# MCU.net
KiCad netlist of a schematic drawn in Altium Designer
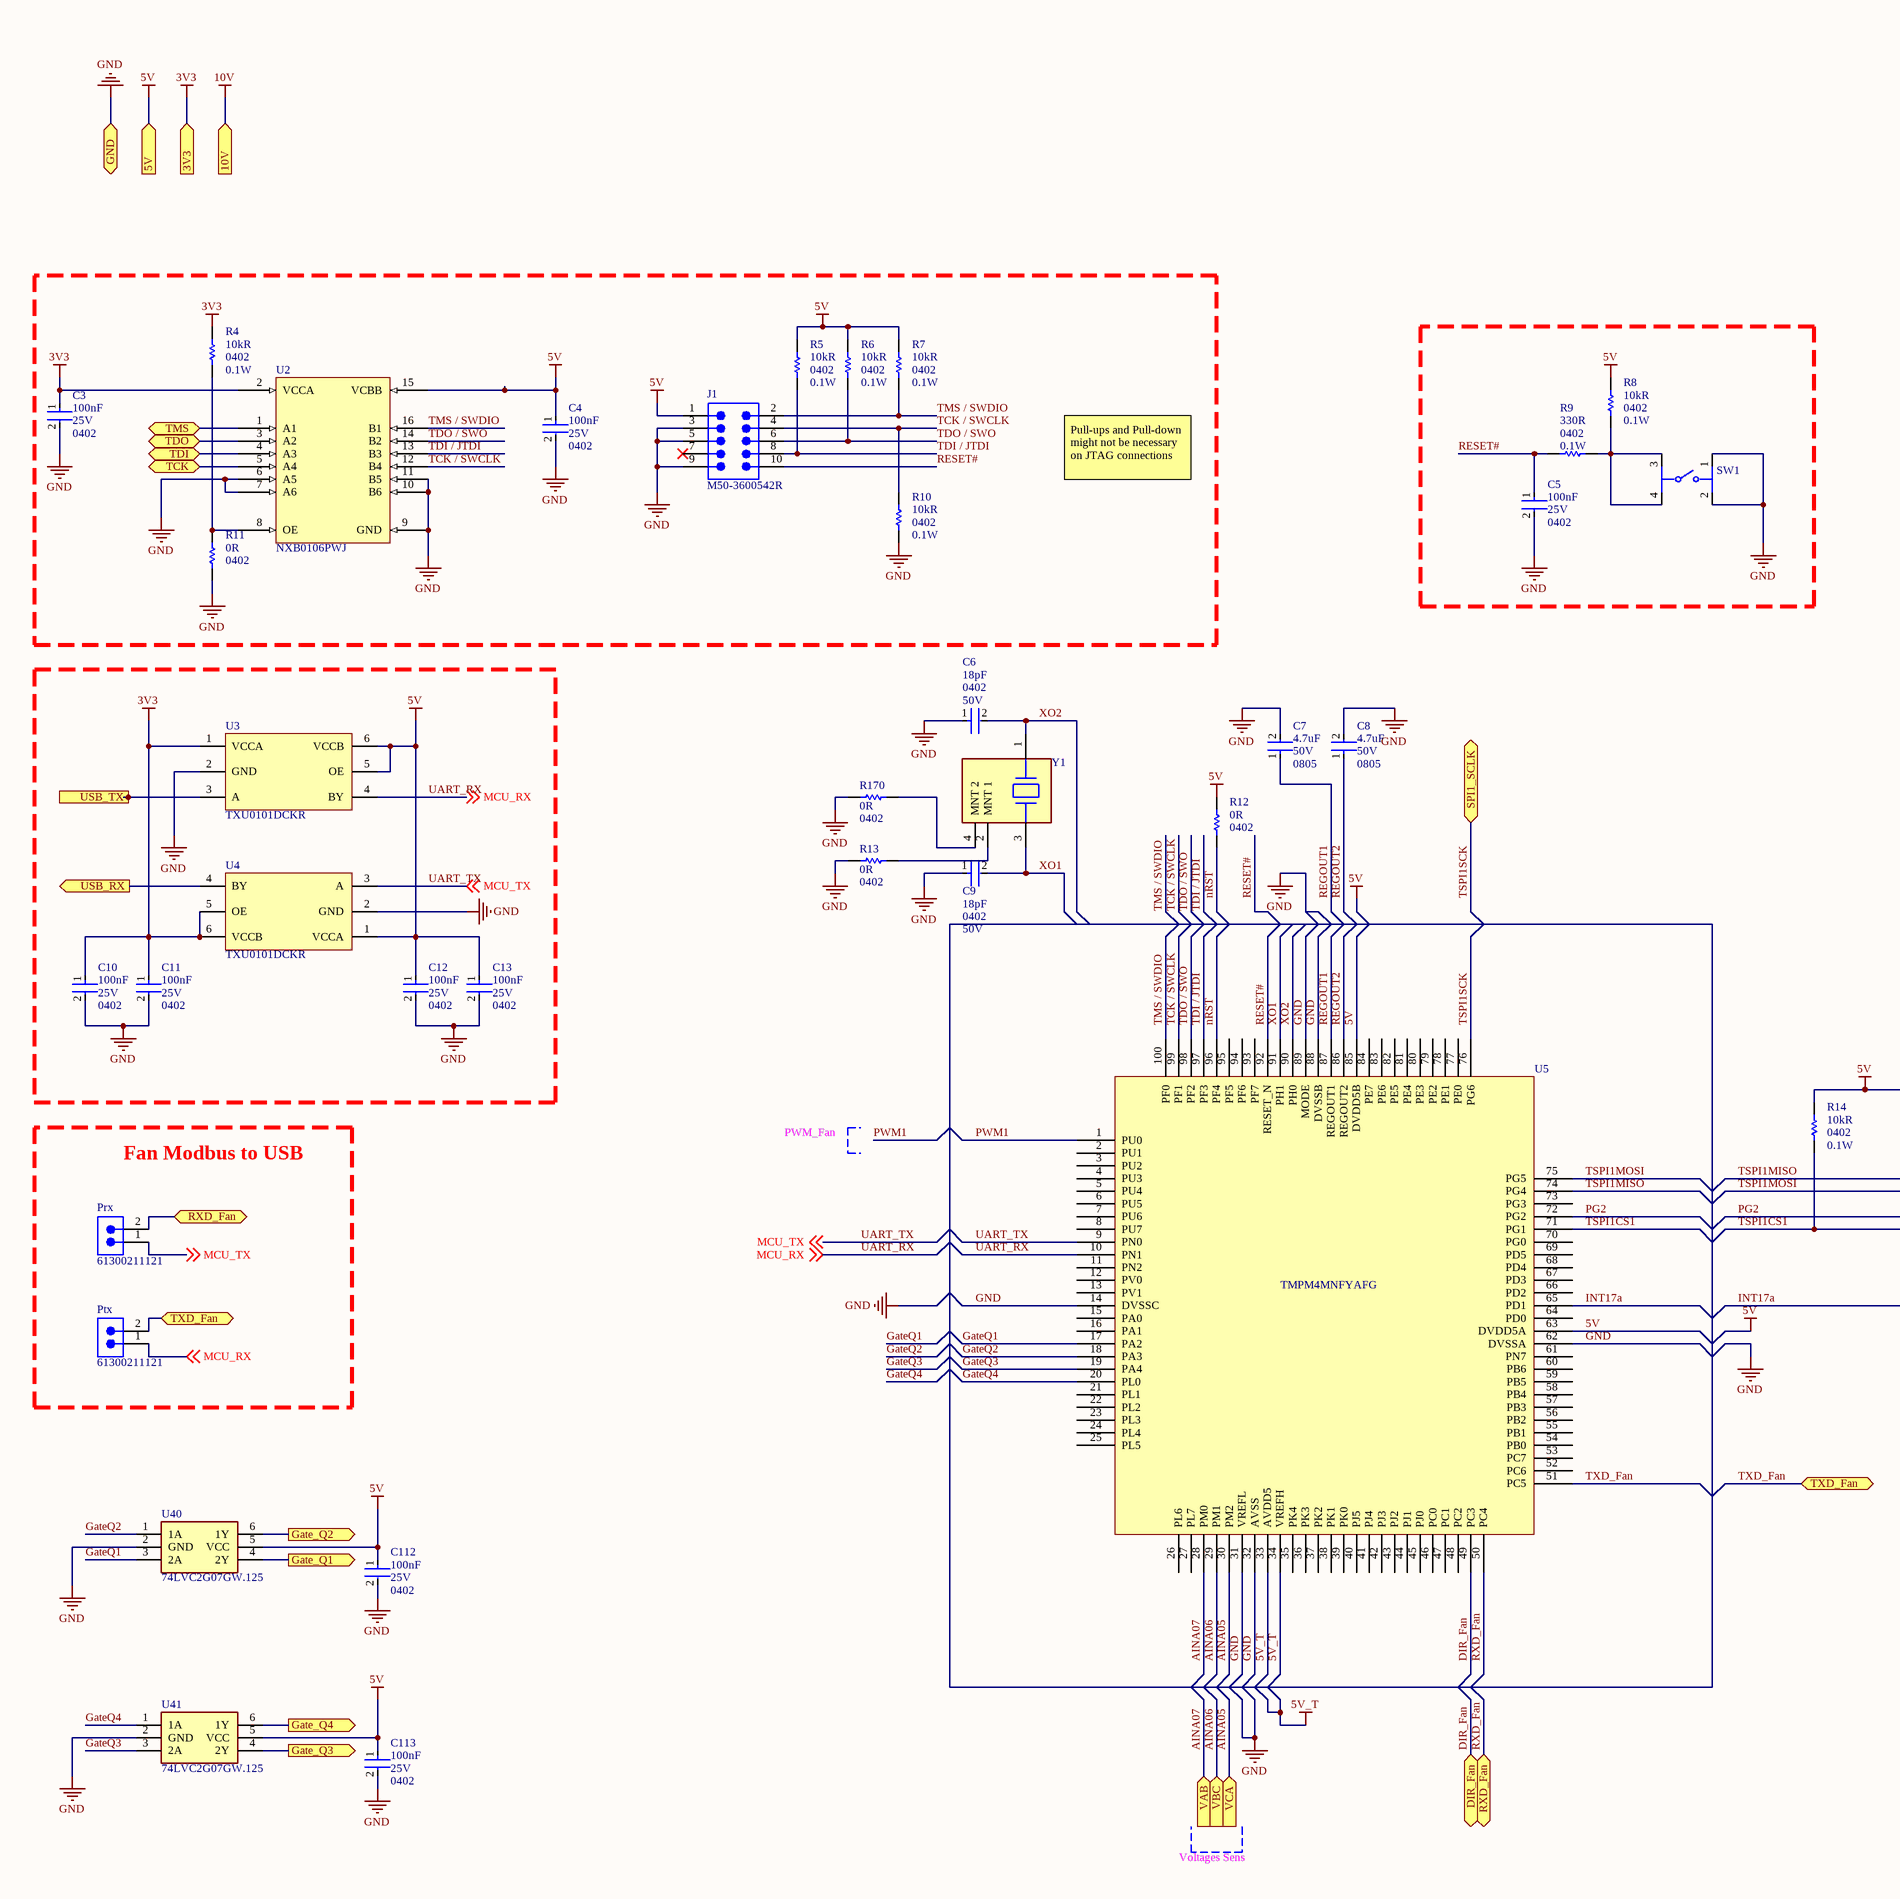
[diagram p0: MCU.SchDoc, left]
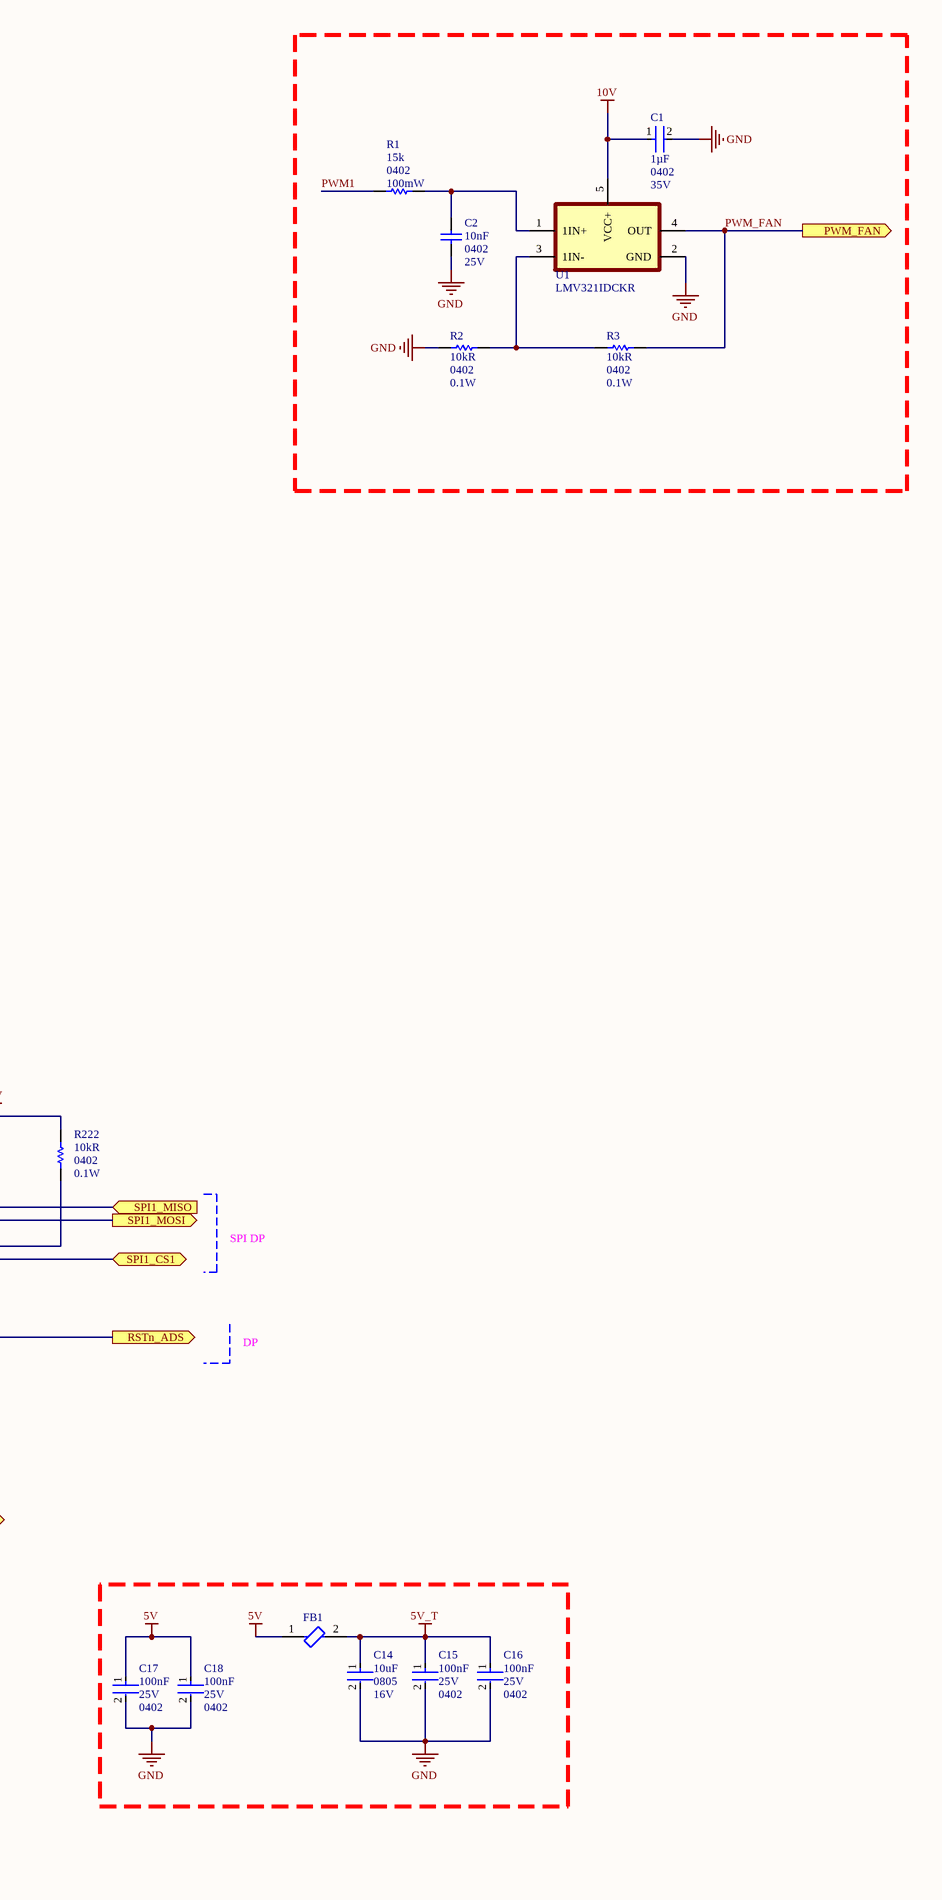
[diagram p1: MCU.SchDoc, right]

(export (version "E")
  (design (tool "Eeschema 10.0.6"))
  (components
    (comp (ref "C1")
      (value "1µF")
      (footprint "FP-C1005-050-0_05-IPC_A")
      (fields
        (field (name "CASE/PACKAGE") "0402")
        (field (name "VOLTAGE RATING") "35V")
        (field (name "Comment") "C1005JB1V105K050BC")
      )
      (libsource (lib "Digital Shovel") (part "b4654b650e69147ec39a6b967a45e02"))
    )
    (comp (ref "C2")
      (value "10nF")
      (footprint "CAPC1005X55X25ML05T10")
      (fields
        (field (name "MANUFACTURER") "Murata")
        (field (name "PACKAGE") "0402")
        (field (name "PARAMETER 1") "25V")
        (field (name "Comment") "GRM155R71E103KA01D")
      )
      (libsource (lib "Digital Shovel") (part "CAP"))
    )
    (comp (ref "C3")
      (value "100nF")
      (footprint "FP-CL830-IPC_A")
      (fields
        (field (name "VOLTAGE RATING") "25V")
        (field (name "CASE/PACKAGE") "0402")
        (field (name "Comment") "CL05B104KA5NNNC")
      )
      (libsource (lib "Digital Shovel") (part "b4654b650e69147ec39a6b967a45e02"))
    )
    (comp (ref "C4")
      (value "100nF")
      (footprint "FP-CL830-IPC_A")
      (fields
        (field (name "VOLTAGE RATING") "25V")
        (field (name "CASE/PACKAGE") "0402")
        (field (name "Comment") "CL05B104KA5NNNC")
      )
      (libsource (lib "Digital Shovel") (part "b4654b650e69147ec39a6b967a45e02"))
    )
    (comp (ref "C5")
      (value "100nF")
      (footprint "FP-CL830-IPC_A")
      (fields
        (field (name "VOLTAGE RATING") "25V")
        (field (name "CASE/PACKAGE") "0402")
        (field (name "Comment") "CL05B104KA5NNNC")
      )
      (libsource (lib "Digital Shovel") (part "b4654b650e69147ec39a6b967a45e02"))
    )
    (comp (ref "C6")
      (value "18pF")
      (footprint "FP-GJM155-0_05-IPC_A")
      (fields
        (field (name "CASE/PACKAGE") "0402")
        (field (name "VOLTAGE RATING") "50V")
        (field (name "Comment") "GJM1555C1H180GB01D")
      )
      (libsource (lib "Digital Shovel") (part "02cd4be3c70576c341d710602a673aa"))
    )
    (comp (ref "C7")
      (value "GRM21BR61H475KE51L")
      (footprint "FP-GRM21B-0_15-IPC_B")
      (description "Chip Multilayer Ceramic Capacitors for General Purpose, 0805, 4.7uF, X5R, 15%, 10%, 50V")
      (fields
        (field (name "CASE/PACKAGE") "0805")
        (field (name "CAPACITANCE") "4.7uF")
        (field (name "VOLTAGE RATING") "50V")
        (field (name "TOLERANCE") "10%")
      )
      (libsource (lib "Altium Content Vault") (part "b4654b650e69147ec39a6b967a45e02"))
    )
    (comp (ref "C8")
      (value "GRM21BR61H475KE51L")
      (footprint "FP-GRM21B-0_15-IPC_B")
      (description "Chip Multilayer Ceramic Capacitors for General Purpose, 0805, 4.7uF, X5R, 15%, 10%, 50V")
      (fields
        (field (name "CASE/PACKAGE") "0805")
        (field (name "CAPACITANCE") "4.7uF")
        (field (name "VOLTAGE RATING") "50V")
        (field (name "TOLERANCE") "10%")
      )
      (libsource (lib "Altium Content Vault") (part "b4654b650e69147ec39a6b967a45e02"))
    )
    (comp (ref "C9")
      (value "18pF")
      (footprint "FP-GJM155-0_05-IPC_A")
      (fields
        (field (name "CASE/PACKAGE") "0402")
        (field (name "VOLTAGE RATING") "50V")
        (field (name "Comment") "GJM1555C1H180GB01D")
      )
      (libsource (lib "Digital Shovel") (part "02cd4be3c70576c341d710602a673aa"))
    )
    (comp (ref "C10")
      (value "100nF")
      (footprint "FP-CL830-IPC_A")
      (fields
        (field (name "VOLTAGE RATING") "25V")
        (field (name "CASE/PACKAGE") "0402")
        (field (name "Comment") "CL05B104KA5NNNC")
      )
      (libsource (lib "Digital Shovel") (part "b4654b650e69147ec39a6b967a45e02"))
    )
    (comp (ref "C11")
      (value "100nF")
      (footprint "FP-CL830-IPC_A")
      (fields
        (field (name "VOLTAGE RATING") "25V")
        (field (name "CASE/PACKAGE") "0402")
        (field (name "Comment") "CL05B104KA5NNNC")
      )
      (libsource (lib "Digital Shovel") (part "b4654b650e69147ec39a6b967a45e02"))
    )
    (comp (ref "C12")
      (value "100nF")
      (footprint "FP-CL830-IPC_A")
      (fields
        (field (name "VOLTAGE RATING") "25V")
        (field (name "CASE/PACKAGE") "0402")
        (field (name "Comment") "CL05B104KA5NNNC")
      )
      (libsource (lib "Digital Shovel") (part "b4654b650e69147ec39a6b967a45e02"))
    )
    (comp (ref "C13")
      (value "100nF")
      (footprint "FP-CL830-IPC_A")
      (fields
        (field (name "VOLTAGE RATING") "25V")
        (field (name "CASE/PACKAGE") "0402")
        (field (name "Comment") "CL05B104KA5NNNC")
      )
      (libsource (lib "Digital Shovel") (part "b4654b650e69147ec39a6b967a45e02"))
    )
    (comp (ref "C14")
      (value "GRM21BR61C106KE15K")
      (footprint "FP-GRM21B-0_1-MFG")
      (description "Chip Multilayer Ceramic Capacitors for General Purpose, 0805, 10uF, X5R, 15%, 10%, 16V")
      (fields
        (field (name "CASE CODE (IMPERIAL)") "0805")
        (field (name "VOLTAGE RATING") "16V")
        (field (name "TOLERANCE") "10%")
        (field (name "VOLTAGE") "16V")
        (field (name "CAPACITANCE") "10uF")
      )
      (libsource (lib "Altium Content Vault") (part "b4654b650e69147ec39a6b967a45e02"))
    )
    (comp (ref "C15")
      (value "100nF")
      (footprint "FP-CL830-IPC_A")
      (fields
        (field (name "VOLTAGE RATING") "25V")
        (field (name "CASE/PACKAGE") "0402")
        (field (name "Comment") "CL05B104KA5NNNC")
      )
      (libsource (lib "Digital Shovel") (part "b4654b650e69147ec39a6b967a45e02"))
    )
    (comp (ref "C16")
      (value "100nF")
      (footprint "FP-CL830-IPC_A")
      (fields
        (field (name "VOLTAGE RATING") "25V")
        (field (name "CASE/PACKAGE") "0402")
        (field (name "Comment") "CL05B104KA5NNNC")
      )
      (libsource (lib "Digital Shovel") (part "b4654b650e69147ec39a6b967a45e02"))
    )
    (comp (ref "C17")
      (value "100nF")
      (footprint "FP-CL830-IPC_A")
      (fields
        (field (name "VOLTAGE RATING") "25V")
        (field (name "CASE/PACKAGE") "0402")
        (field (name "Comment") "CL05B104KA5NNNC")
      )
      (libsource (lib "Digital Shovel") (part "b4654b650e69147ec39a6b967a45e02"))
    )
    (comp (ref "C18")
      (value "100nF")
      (footprint "FP-CL830-IPC_A")
      (fields
        (field (name "VOLTAGE RATING") "25V")
        (field (name "CASE/PACKAGE") "0402")
        (field (name "Comment") "CL05B104KA5NNNC")
      )
      (libsource (lib "Digital Shovel") (part "b4654b650e69147ec39a6b967a45e02"))
    )
    (comp (ref "C112")
      (value "100nF")
      (footprint "FP-CL830-IPC_A")
      (fields
        (field (name "VOLTAGE RATING") "25V")
        (field (name "CASE/PACKAGE") "0402")
        (field (name "Comment") "CL05B104KA5NNNC")
      )
      (libsource (lib "Digital Shovel") (part "b4654b650e69147ec39a6b967a45e02"))
    )
    (comp (ref "C113")
      (value "100nF")
      (footprint "FP-CL830-IPC_A")
      (fields
        (field (name "VOLTAGE RATING") "25V")
        (field (name "CASE/PACKAGE") "0402")
        (field (name "Comment") "CL05B104KA5NNNC")
      )
      (libsource (lib "Digital Shovel") (part "b4654b650e69147ec39a6b967a45e02"))
    )
    (comp (ref "FB1")
      (value "MPZ2012S221AT000")
      (footprint "FP-MPZ2012-MFG")
      (description "FERRITE BEAD 220 OHM 0805 1LN")
      (fields (field (name "TOLERANCE") "25%"))
      (libsource (lib "Altium Content Vault") (part "5f30dd21d616792df468990f7003faa"))
    )
    (comp (ref "J1")
      (value "M50-3600542R")
      (footprint "FP-M50-3600542R-MFG")
      (libsource (lib "Digital Shovel") (part "CMP-00130-1"))
    )
    (comp (ref "Prx")
      (value "61300211121")
      (footprint "61300211121")
      (description "WR-PHD Pin Header, THT, Vertical, pitch 2.54mm, 1 Row, 2P")
      (fields (field (name "MANUFACTURER") "Wurth Elektronik"))
      (libsource (lib "Digital Shovel") (part "62000211121"))
    )
    (comp (ref "Ptx")
      (value "61300211121")
      (footprint "61300211121")
      (description "WR-PHD Pin Header, THT, Vertical, pitch 2.54mm, 1 Row, 2P")
      (fields (field (name "MANUFACTURER") "Wurth Elektronik"))
      (libsource (lib "Digital Shovel") (part "62000211121"))
    )
    (comp (ref "R1")
      (value "15k")
      (footprint "RESC1005X40X25LL10T10")
      (fields
        (field (name "TOLERANCE") "1%")
        (field (name "CASE/PACKAGE") "0402")
        (field (name "POWER") "100mW")
        (field (name "Comment") "RK73H1ETTP1502F")
      )
      (libsource (lib "Digital Shovel") (part "RES"))
    )
    (comp (ref "R2")
      (value "10kR")
      (footprint "RESC1005X40X25LL10T10")
      (fields
        (field (name "PACKAGE") "0402")
        (field (name "POWER") "0.1W")
        (field (name "Comment") "RK73H1ETTP1002F")
      )
      (libsource (lib "Digital Shovel") (part "RES"))
    )
    (comp (ref "R3")
      (value "10kR")
      (footprint "RESC1005X40X25LL10T10")
      (fields
        (field (name "PACKAGE") "0402")
        (field (name "POWER") "0.1W")
        (field (name "Comment") "RK73H1ETTP1002F")
      )
      (libsource (lib "Digital Shovel") (part "RES"))
    )
    (comp (ref "R4")
      (value "10kR")
      (footprint "RESC1005X40X25LL10T10")
      (fields
        (field (name "PACKAGE") "0402")
        (field (name "POWER RATING") "0.1W")
        (field (name "Comment") "RK73H1ETTP1002F")
      )
      (libsource (lib "Digital Shovel") (part "RES"))
    )
    (comp (ref "R5")
      (value "10kR")
      (footprint "RESC1005X40X25LL10T10")
      (fields
        (field (name "PACKAGE") "0402")
        (field (name "POWER RATING") "0.1W")
        (field (name "Comment") "RK73H1ETTP1002F")
      )
      (libsource (lib "Digital Shovel") (part "RES"))
    )
    (comp (ref "R6")
      (value "10kR")
      (footprint "RESC1005X40X25LL10T10")
      (fields
        (field (name "PACKAGE") "0402")
        (field (name "POWER RATING") "0.1W")
        (field (name "Comment") "RK73H1ETTP1002F")
      )
      (libsource (lib "Digital Shovel") (part "RES"))
    )
    (comp (ref "R7")
      (value "10kR")
      (footprint "RESC1005X40X25LL10T10")
      (fields
        (field (name "PACKAGE") "0402")
        (field (name "POWER RATING") "0.1W")
        (field (name "Comment") "RK73H1ETTP1002F")
      )
      (libsource (lib "Digital Shovel") (part "RES"))
    )
    (comp (ref "R8")
      (value "10kR")
      (footprint "RESC1005X40X25LL10T10")
      (fields
        (field (name "PACKAGE") "0402")
        (field (name "POWER RATING") "0.1W")
        (field (name "Comment") "RK73H1ETTP1002F")
      )
      (libsource (lib "Digital Shovel") (part "RES"))
    )
    (comp (ref "R9")
      (value "330R")
      (footprint "RESC1005X40X25LL10T10")
      (fields
        (field (name "PACKAGE") "0402")
        (field (name "POWER RATING") "0.1W")
        (field (name "Comment") "RK73H1ETTP3300F")
      )
      (libsource (lib "Digital Shovel") (part "RES"))
    )
    (comp (ref "R10")
      (value "10kR")
      (footprint "RESC1005X40X25LL10T10")
      (fields
        (field (name "PACKAGE") "0402")
        (field (name "POWER RATING") "0.1W")
        (field (name "Comment") "RK73H1ETTP1002F")
      )
      (libsource (lib "Digital Shovel") (part "RES"))
    )
    (comp (ref "R11")
      (value "0R")
      (footprint "FP-RK73Z1E-IPC_B")
      (description "Metal Glaze/thick Film, 0ohm, Surface Mount, 0402")
      (fields (field (name "PACKAGE") "0402") (field (name "Comment") "RK73Z1ETTP"))
      (libsource (lib "Digital Shovel") (part "1029c3af85768c4190bb7ad29bc67b5"))
    )
    (comp (ref "R12")
      (value "0R")
      (footprint "FP-RK73Z1E-IPC_B")
      (description "Metal Glaze/thick Film, 0ohm, Surface Mount, 0402")
      (fields (field (name "PACKAGE") "0402") (field (name "Comment") "RK73Z1ETTP"))
      (libsource (lib "Digital Shovel") (part "1029c3af85768c4190bb7ad29bc67b5"))
    )
    (comp (ref "R13")
      (value "0R")
      (footprint "FP-RK73Z1E-IPC_B")
      (description "Metal Glaze/thick Film, 0ohm, Surface Mount, 0402")
      (fields (field (name "PACKAGE") "0402") (field (name "Comment") "RK73Z1ETTP"))
      (libsource (lib "Digital Shovel") (part "1029c3af85768c4190bb7ad29bc67b5"))
    )
    (comp (ref "R14")
      (value "10kR")
      (footprint "RESC1005X40X25LL10T10")
      (fields
        (field (name "PACKAGE") "0402")
        (field (name "POWER RATING") "0.1W")
        (field (name "Comment") "RK73H1ETTP1002F")
      )
      (libsource (lib "Digital Shovel") (part "RES"))
    )
    (comp (ref "R170")
      (value "0R")
      (footprint "FP-RK73Z1E-IPC_B")
      (description "Metal Glaze/thick Film, 0ohm, Surface Mount, 0402")
      (fields (field (name "PACKAGE") "0402") (field (name "Comment") "RK73Z1ETTP"))
      (libsource (lib "Digital Shovel") (part "1029c3af85768c4190bb7ad29bc67b5"))
    )
    (comp (ref "R222")
      (value "10kR")
      (footprint "RESC1005X40X25LL10T10")
      (fields
        (field (name "PACKAGE") "0402")
        (field (name "POWER RATING") "0.1W")
        (field (name "Comment") "RK73H1ETTP1002F")
      )
      (libsource (lib "Digital Shovel") (part "RES"))
    )
    (comp (ref "SW1")
      (value "PTS810SJM250SMTRLFS")
      (footprint "FP-PTS810SJM250SMTRLFS-MFG")
      (fields (field (name "MANUFACTURER") "C&K"))
      (libsource (lib "Digital Shovel") (part "1adf0dd01260c80cf25a44bfd6b99ba"))
    )
    (comp (ref "U1")
      (value "LMV321IDCKR")
      (footprint "LMV321IDCKR-Footprint-1")
      (description "Operational Amplifier, 1 Func, 7000uV Offset-Max, BIPolar, PDSO5")
      (libsource (lib "Digital Shovel") (part "TLV9104QPWRQ1"))
    )
    (comp (ref "U2")
      (value "NXB0106PWJ")
      (footprint "TSOP65P640X120-16N")
      (description "NXB0106 - Dual supply translating transceiver; auto direction sensing; 3-state")
      (libsource (lib "Digital Shovel") (part "NXB0106PWJ-Symbol-1"))
    )
    (comp (ref "U3")
      (value "TXU0101DCKR")
      (footprint "FP-DCK0006A-MFG")
      (description "Single channel fixed-direction level shifter 6-SC70 -40 to 125")
      (libsource (lib "Digital Shovel") (part "TXU0101DCKR"))
    )
    (comp (ref "U4")
      (value "TXU0101DCKR")
      (footprint "FP-DCK0006A-MFG")
      (description "Single channel fixed-direction level shifter 6-SC70 -40 to 125")
      (libsource (lib "") (part "TXU0101DCKR_1"))
    )
    (comp (ref "U5")
      (value "TMPM4MNFYAFG")
      (footprint "TSQFP50P1600X1600X145-100N")
      (description "Toshiba Micro")
      (libsource (lib "Digital Shovel") (part "TMPM4MNFYAFG"))
    )
    (comp (ref "U40")
      (value "74LVC2G07GW.125")
      (footprint "74LVC2G07GW.125-Footprint-1")
      (description "Buffer, Non-Inverting 2 Element 1 Bit per Element Open Drain Output 6-TSSOP")
      (libsource (lib "Digital Shovel") (part "74LVC2G07GW.125-Symbol-1"))
    )
    (comp (ref "U41")
      (value "74LVC2G07GW.125")
      (footprint "74LVC2G07GW.125-Footprint-1")
      (description "Buffer, Non-Inverting 2 Element 1 Bit per Element Open Drain Output 6-TSSOP")
      (libsource (lib "Digital Shovel") (part "74LVC2G07GW.125-Symbol-1"))
    )
    (comp (ref "Y1")
      (value "ABM10-166-12.000MHZ-T3")
      (footprint "FP-ABM10-166-167-MFG")
      (description "Crystal 12MHz ±10ppm (Tol) ±10ppm (Stability) 8pF FUND 125Ohm 4-Pin SMD T/R")
      (fields (field (name "MANUFACTURER") "TI"))
      (libsource (lib "Digital Shovel") (part "c1e6c4da84e2560fa339d1e93faccc5"))
    )
  )
  (nets
    (net (code "1") (name "/AINA05") (class "Default")
      (node (ref "U5") (pin "30") (pinfunction "PM2_30") (pintype "passive"))
    )
    (net (code "2") (name "/AINA06") (class "Default")
      (node (ref "U5") (pin "29") (pinfunction "PM1_29") (pintype "passive"))
    )
    (net (code "3") (name "/AINA07") (class "Default")
      (node (ref "U5") (pin "28") (pinfunction "PM0_28") (pintype "passive"))
    )
    (net (code "4") (name "/DIR_Fan") (class "Default")
      (node (ref "U5") (pin "49") (pinfunction "PC3_49") (pintype "passive"))
    )
    (net (code "5") (name "/GateQ1") (class "Default")
      (node (ref "U40") (pin "3") (pinfunction "2A_3") (pintype "passive"))
      (node (ref "U5") (pin "17") (pinfunction "PA2_17") (pintype "passive"))
    )
    (net (code "6") (name "/GateQ2") (class "Default")
      (node (ref "U40") (pin "1") (pinfunction "1A_1") (pintype "passive"))
      (node (ref "U5") (pin "18") (pinfunction "PA3_18") (pintype "passive"))
    )
    (net (code "7") (name "/GateQ3") (class "Default")
      (node (ref "U41") (pin "3") (pinfunction "2A_3") (pintype "passive"))
      (node (ref "U5") (pin "19") (pinfunction "PA4_19") (pintype "passive"))
    )
    (net (code "8") (name "/GateQ4") (class "Default")
      (node (ref "U41") (pin "1") (pinfunction "1A_1") (pintype "passive"))
      (node (ref "U5") (pin "20") (pinfunction "PL0_20") (pintype "passive"))
    )
    (net (code "9") (name "/Gate_Q1") (class "Default")
      (node (ref "U40") (pin "4") (pinfunction "2Y_4") (pintype "passive"))
    )
    (net (code "10") (name "/Gate_Q2") (class "Default")
      (node (ref "U40") (pin "6") (pinfunction "1Y_6") (pintype "passive"))
    )
    (net (code "11") (name "/Gate_Q3") (class "Default")
      (node (ref "U41") (pin "4") (pinfunction "2Y_4") (pintype "passive"))
    )
    (net (code "12") (name "/Gate_Q4") (class "Default")
      (node (ref "U41") (pin "6") (pinfunction "1Y_6") (pintype "passive"))
    )
    (net (code "13") (name "/INT17a") (class "Default")
      (node (ref "U5") (pin "65") (pinfunction "PD1_65") (pintype "passive"))
    )
    (net (code "14") (name "/PG2") (class "Default")
      (node (ref "R222") (pin "1") (pinfunction "1_1") (pintype "passive"))
      (node (ref "U5") (pin "72") (pinfunction "PG2_72") (pintype "passive"))
    )
    (net (code "15") (name "/PWM1") (class "Default")
      (node (ref "R1") (pin "1") (pinfunction "1_1") (pintype "passive"))
      (node (ref "U5") (pin "1") (pinfunction "PU0_1") (pintype "passive"))
    )
    (net (code "16") (name "/PWM_FAN") (class "Default")
      (node (ref "R3") (pin "2") (pinfunction "2_2") (pintype "passive"))
      (node (ref "U1") (pin "4") (pinfunction "OUT_4") (pintype "passive"))
    )
    (net (code "17") (name "/REGOUT1") (class "Default")
      (node (ref "C7") (pin "1") (pinfunction "1_1") (pintype "passive"))
      (node (ref "U5") (pin "87") (pinfunction "REGOUT1_87") (pintype "passive"))
    )
    (net (code "18") (name "/REGOUT2") (class "Default")
      (node (ref "C8") (pin "1") (pinfunction "1_1") (pintype "passive"))
      (node (ref "U5") (pin "86") (pinfunction "REGOUT2_86") (pintype "passive"))
    )
    (net (code "19") (name "/RESET#") (class "Default")
      (node (ref "C5") (pin "1") (pinfunction "1_1") (pintype "passive"))
      (node (ref "J1") (pin "10") (pinfunction "10_10") (pintype "passive"))
      (node (ref "R9") (pin "1") (pinfunction "1_1") (pintype "passive"))
      (node (ref "U5") (pin "92") (pinfunction "RESET_N_92") (pintype "passive"))
    )
    (net (code "20") (name "/RXD_Fan") (class "Default")
      (node (ref "Prx") (pin "2") (pinfunction "2_2") (pintype "passive"))
      (node (ref "U5") (pin "50") (pinfunction "PC4_50") (pintype "passive"))
    )
    (net (code "21") (name "/TCK") (class "Default")
      (node (ref "U2") (pin "5") (pinfunction "A4_5") (pintype "input"))
    )
    (net (code "22") (name "/TCK {slash} SWCLK") (class "Default")
      (node (ref "J1") (pin "4") (pinfunction "4_4") (pintype "passive"))
      (node (ref "R10") (pin "2") (pinfunction "2_2") (pintype "passive"))
      (node (ref "U2") (pin "12") (pinfunction "B4_12") (pintype "input"))
      (node (ref "U5") (pin "99") (pinfunction "PF1_99") (pintype "passive"))
    )
    (net (code "23") (name "/TDI") (class "Default")
      (node (ref "U2") (pin "4") (pinfunction "A3_4") (pintype "input"))
    )
    (net (code "24") (name "/TDI {slash} JTDI") (class "Default")
      (node (ref "J1") (pin "8") (pinfunction "8_8") (pintype "passive"))
      (node (ref "R5") (pin "1") (pinfunction "1_1") (pintype "passive"))
      (node (ref "U2") (pin "13") (pinfunction "B3_13") (pintype "input"))
      (node (ref "U5") (pin "97") (pinfunction "PF3_97") (pintype "passive"))
    )
    (net (code "25") (name "/TDO") (class "Default")
      (node (ref "U2") (pin "3") (pinfunction "A2_3") (pintype "input"))
    )
    (net (code "26") (name "/TDO {slash} SWO") (class "Default")
      (node (ref "J1") (pin "6") (pinfunction "6_6") (pintype "passive"))
      (node (ref "R6") (pin "1") (pinfunction "1_1") (pintype "passive"))
      (node (ref "U2") (pin "14") (pinfunction "B2_14") (pintype "input"))
      (node (ref "U5") (pin "98") (pinfunction "PF2_98") (pintype "passive"))
    )
    (net (code "27") (name "/TMS") (class "Default")
      (node (ref "U2") (pin "1") (pinfunction "A1_1") (pintype "input"))
    )
    (net (code "28") (name "/TMS {slash} SWDIO") (class "Default")
      (node (ref "J1") (pin "2") (pinfunction "2_2") (pintype "passive"))
      (node (ref "R7") (pin "1") (pinfunction "1_1") (pintype "passive"))
      (node (ref "U2") (pin "16") (pinfunction "B1_16") (pintype "input"))
      (node (ref "U5") (pin "100") (pinfunction "PF0_100") (pintype "passive"))
    )
    (net (code "29") (name "/TSPI1CS1") (class "Default")
      (node (ref "R14") (pin "1") (pinfunction "1_1") (pintype "passive"))
      (node (ref "U5") (pin "71") (pinfunction "PG1_71") (pintype "passive"))
    )
    (net (code "30") (name "/TSPI1MISO") (class "Default")
      (node (ref "U5") (pin "74") (pinfunction "PG4_74") (pintype "passive"))
    )
    (net (code "31") (name "/TSPI1MOSI") (class "Default")
      (node (ref "U5") (pin "75") (pinfunction "PG5_75") (pintype "passive"))
    )
    (net (code "32") (name "/TSPI1SCK") (class "Default")
      (node (ref "U5") (pin "76") (pinfunction "PG6_76") (pintype "passive"))
    )
    (net (code "33") (name "/TXD_Fan") (class "Default")
      (node (ref "Ptx") (pin "2") (pinfunction "2_2") (pintype "passive"))
      (node (ref "U5") (pin "51") (pinfunction "PC5_51") (pintype "passive"))
    )
    (net (code "34") (name "/USB_RX") (class "Default")
      (node (ref "U4") (pin "4") (pinfunction "BY_4") (pintype "passive"))
    )
    (net (code "35") (name "/USB_TX") (class "Default")
      (node (ref "U3") (pin "3") (pinfunction "A_3") (pintype "passive"))
    )
    (net (code "36") (name "/XO1") (class "Default")
      (node (ref "C9") (pin "2") (pinfunction "2_2") (pintype "passive"))
      (node (ref "U5") (pin "91") (pinfunction "PH1_91") (pintype "passive"))
      (node (ref "Y1") (pin "3") (pinfunction "3_3") (pintype "passive"))
    )
    (net (code "37") (name "/XO2") (class "Default")
      (node (ref "C6") (pin "2") (pinfunction "2_2") (pintype "passive"))
      (node (ref "U5") (pin "90") (pinfunction "PH0_90") (pintype "passive"))
      (node (ref "Y1") (pin "1") (pinfunction "1_1") (pintype "passive"))
    )
    (net (code "38") (name "/nRST") (class "Default")
      (node (ref "R12") (pin "1") (pinfunction "1_1") (pintype "passive"))
      (node (ref "U5") (pin "96") (pinfunction "PF4_96") (pintype "passive"))
    )
    (net (code "39") (name "3V3") (class "Default")
      (node (ref "C10") (pin "1") (pinfunction "1_1") (pintype "passive"))
      (node (ref "C11") (pin "1") (pinfunction "1_1") (pintype "passive"))
      (node (ref "C3") (pin "1") (pinfunction "1_1") (pintype "passive"))
      (node (ref "R4") (pin "2") (pinfunction "2_2") (pintype "passive"))
      (node (ref "U2") (pin "2") (pinfunction "VCCA_2") (pintype "input"))
      (node (ref "U3") (pin "1") (pinfunction "VCCA_1") (pintype "passive"))
      (node (ref "U4") (pin "5") (pinfunction "OE_5") (pintype "passive"))
      (node (ref "U4") (pin "6") (pinfunction "VCCB_6") (pintype "passive"))
    )
    (net (code "40") (name "5V") (class "Default")
      (node (ref "C112") (pin "1") (pinfunction "1_1") (pintype "passive"))
      (node (ref "C113") (pin "1") (pinfunction "1_1") (pintype "passive"))
      (node (ref "C12") (pin "1") (pinfunction "1_1") (pintype "passive"))
      (node (ref "C13") (pin "1") (pinfunction "1_1") (pintype "passive"))
      (node (ref "C17") (pin "1") (pinfunction "1_1") (pintype "passive"))
      (node (ref "C18") (pin "1") (pinfunction "1_1") (pintype "passive"))
      (node (ref "C4") (pin "1") (pinfunction "1_1") (pintype "passive"))
      (node (ref "FB1") (pin "1") (pinfunction "1_1") (pintype "passive"))
      (node (ref "J1") (pin "1") (pinfunction "1_1") (pintype "passive"))
      (node (ref "R12") (pin "2") (pinfunction "2_2") (pintype "passive"))
      (node (ref "R14") (pin "2") (pinfunction "2_2") (pintype "passive"))
      (node (ref "R222") (pin "2") (pinfunction "2_2") (pintype "passive"))
      (node (ref "R5") (pin "2") (pinfunction "2_2") (pintype "passive"))
      (node (ref "R6") (pin "2") (pinfunction "2_2") (pintype "passive"))
      (node (ref "R7") (pin "2") (pinfunction "2_2") (pintype "passive"))
      (node (ref "R8") (pin "2") (pinfunction "2_2") (pintype "passive"))
      (node (ref "U2") (pin "15") (pinfunction "VCBB_15") (pintype "input"))
      (node (ref "U3") (pin "5") (pinfunction "OE_5") (pintype "passive"))
      (node (ref "U3") (pin "6") (pinfunction "VCCB_6") (pintype "passive"))
      (node (ref "U4") (pin "1") (pinfunction "VCCA_1") (pintype "passive"))
      (node (ref "U40") (pin "5") (pinfunction "VCC_5") (pintype "passive"))
      (node (ref "U41") (pin "5") (pinfunction "VCC_5") (pintype "passive"))
      (node (ref "U5") (pin "63") (pinfunction "DVDD5A_63") (pintype "passive"))
      (node (ref "U5") (pin "85") (pinfunction "DVDD5B_85") (pintype "passive"))
    )
    (net (code "41") (name "5V_T") (class "Default")
      (node (ref "C14") (pin "1") (pinfunction "1_1") (pintype "passive"))
      (node (ref "C15") (pin "1") (pinfunction "1_1") (pintype "passive"))
      (node (ref "C16") (pin "1") (pinfunction "1_1") (pintype "passive"))
      (node (ref "FB1") (pin "2") (pinfunction "2_2") (pintype "passive"))
      (node (ref "U5") (pin "33") (pinfunction "AVDD5_33") (pintype "passive"))
      (node (ref "U5") (pin "34") (pinfunction "VREFH_34") (pintype "passive"))
    )
    (net (code "42") (name "10V") (class "Default")
      (node (ref "C1") (pin "1") (pinfunction "1_1") (pintype "passive"))
      (node (ref "U1") (pin "5") (pinfunction "VCC+_5") (pintype "passive"))
    )
    (net (code "43") (name "GND") (class "Default")
      (node (ref "C1") (pin "2") (pinfunction "2_2") (pintype "passive"))
      (node (ref "C10") (pin "2") (pinfunction "2_2") (pintype "passive"))
      (node (ref "C11") (pin "2") (pinfunction "2_2") (pintype "passive"))
      (node (ref "C112") (pin "2") (pinfunction "2_2") (pintype "passive"))
      (node (ref "C113") (pin "2") (pinfunction "2_2") (pintype "passive"))
      (node (ref "C12") (pin "2") (pinfunction "2_2") (pintype "passive"))
      (node (ref "C13") (pin "2") (pinfunction "2_2") (pintype "passive"))
      (node (ref "C14") (pin "2") (pinfunction "2_2") (pintype "passive"))
      (node (ref "C15") (pin "2") (pinfunction "2_2") (pintype "passive"))
      (node (ref "C16") (pin "2") (pinfunction "2_2") (pintype "passive"))
      (node (ref "C17") (pin "2") (pinfunction "2_2") (pintype "passive"))
      (node (ref "C18") (pin "2") (pinfunction "2_2") (pintype "passive"))
      (node (ref "C2") (pin "1") (pinfunction "1_1") (pintype "passive"))
      (node (ref "C3") (pin "2") (pinfunction "2_2") (pintype "passive"))
      (node (ref "C4") (pin "2") (pinfunction "2_2") (pintype "passive"))
      (node (ref "C5") (pin "2") (pinfunction "2_2") (pintype "passive"))
      (node (ref "C6") (pin "1") (pinfunction "1_1") (pintype "passive"))
      (node (ref "C7") (pin "2") (pinfunction "2_2") (pintype "passive"))
      (node (ref "C8") (pin "2") (pinfunction "2_2") (pintype "passive"))
      (node (ref "C9") (pin "1") (pinfunction "1_1") (pintype "passive"))
      (node (ref "J1") (pin "3") (pinfunction "3_3") (pintype "passive"))
      (node (ref "J1") (pin "5") (pinfunction "5_5") (pintype "passive"))
      (node (ref "J1") (pin "9") (pinfunction "9_9") (pintype "passive"))
      (node (ref "R10") (pin "1") (pinfunction "1_1") (pintype "passive"))
      (node (ref "R11") (pin "1") (pinfunction "1_1") (pintype "passive"))
      (node (ref "R13") (pin "2") (pinfunction "2_2") (pintype "passive"))
      (node (ref "R170") (pin "2") (pinfunction "2_2") (pintype "passive"))
      (node (ref "R2") (pin "1") (pinfunction "1_1") (pintype "passive"))
      (node (ref "SW1") (pin "1") (pinfunction "1_1") (pintype "passive"))
      (node (ref "SW1") (pin "2") (pinfunction "2_2") (pintype "passive"))
      (node (ref "U1") (pin "2") (pinfunction "GND_2") (pintype "passive"))
      (node (ref "U2") (pin "10") (pinfunction "B6_10") (pintype "input"))
      (node (ref "U2") (pin "11") (pinfunction "B5_11") (pintype "input"))
      (node (ref "U2") (pin "6") (pinfunction "A5_6") (pintype "input"))
      (node (ref "U2") (pin "7") (pinfunction "A6_7") (pintype "input"))
      (node (ref "U2") (pin "9") (pinfunction "GND_9") (pintype "input"))
      (node (ref "U3") (pin "2") (pinfunction "GND_2") (pintype "passive"))
      (node (ref "U4") (pin "2") (pinfunction "GND_2") (pintype "passive"))
      (node (ref "U40") (pin "2") (pinfunction "GND_2") (pintype "passive"))
      (node (ref "U41") (pin "2") (pinfunction "GND_2") (pintype "passive"))
      (node (ref "U5") (pin "14") (pinfunction "DVSSC_14") (pintype "passive"))
      (node (ref "U5") (pin "31") (pinfunction "VREFL_31") (pintype "passive"))
      (node (ref "U5") (pin "32") (pinfunction "AVSS_32") (pintype "passive"))
      (node (ref "U5") (pin "62") (pinfunction "DVSSA_62") (pintype "passive"))
      (node (ref "U5") (pin "88") (pinfunction "DVSSB_88") (pintype "passive"))
      (node (ref "U5") (pin "89") (pinfunction "MODE_89") (pintype "passive"))
    )
    (net (code "44") (name "MCU_RX") (class "Default")
      (node (ref "Ptx") (pin "1") (pinfunction "1_1") (pintype "passive"))
      (node (ref "U3") (pin "4") (pinfunction "BY_4") (pintype "passive"))
      (node (ref "U5") (pin "10") (pinfunction "PN1_10") (pintype "passive"))
    )
    (net (code "45") (name "MCU_TX") (class "Default")
      (node (ref "Prx") (pin "1") (pinfunction "1_1") (pintype "passive"))
      (node (ref "U4") (pin "3") (pinfunction "A_3") (pintype "passive"))
      (node (ref "U5") (pin "9") (pinfunction "PN0_9") (pintype "passive"))
    )
    (net (code "46") (name "Net-(R8-Pad1)") (class "Default")
      (node (ref "R8") (pin "1") (pinfunction "1_1") (pintype "passive"))
      (node (ref "R9") (pin "2") (pinfunction "2_2") (pintype "passive"))
      (node (ref "SW1") (pin "3") (pinfunction "3_3") (pintype "passive"))
      (node (ref "SW1") (pin "4") (pinfunction "4_4") (pintype "passive"))
    )
    (net (code "47") (name "Net-(U1-1IN+)") (class "Default")
      (node (ref "C2") (pin "2") (pinfunction "2_2") (pintype "passive"))
      (node (ref "R1") (pin "2") (pinfunction "2_2") (pintype "passive"))
      (node (ref "U1") (pin "1") (pinfunction "1IN+_1") (pintype "passive"))
    )
    (net (code "48") (name "Net-(U1-1IN-)") (class "Default")
      (node (ref "R2") (pin "2") (pinfunction "2_2") (pintype "passive"))
      (node (ref "R3") (pin "1") (pinfunction "1_1") (pintype "passive"))
      (node (ref "U1") (pin "3") (pinfunction "1IN-_3") (pintype "passive"))
    )
    (net (code "49") (name "Net-(U2-OE)") (class "Default")
      (node (ref "R11") (pin "2") (pinfunction "2_2") (pintype "passive"))
      (node (ref "R4") (pin "1") (pinfunction "1_1") (pintype "passive"))
      (node (ref "U2") (pin "8") (pinfunction "OE_8") (pintype "input"))
    )
    (net (code "50") (name "Net-(Y1-MNT_1)") (class "Default")
      (node (ref "R13") (pin "1") (pinfunction "1_1") (pintype "passive"))
      (node (ref "Y1") (pin "2") (pinfunction "MNT_1_2") (pintype "passive"))
    )
    (net (code "51") (name "Net-(Y1-MNT_2)") (class "Default")
      (node (ref "R170") (pin "1") (pinfunction "1_1") (pintype "passive"))
      (node (ref "Y1") (pin "4") (pinfunction "MNT_2_4") (pintype "passive"))
    )
    (net (code "52") (name "unconnected-(J1-Pad7)") (class "Default")
      (node (ref "J1") (pin "7") (pinfunction "7_7") (pintype "passive+no_connect"))
    )
    (net (code "53") (name "unconnected-(U5-PA0-Pad15)") (class "Default")
      (node (ref "U5") (pin "15") (pinfunction "PA0_15") (pintype "passive"))
    )
    (net (code "54") (name "unconnected-(U5-PA1-Pad16)") (class "Default")
      (node (ref "U5") (pin "16") (pinfunction "PA1_16") (pintype "passive"))
    )
    (net (code "55") (name "unconnected-(U5-PB0-Pad54)") (class "Default")
      (node (ref "U5") (pin "54") (pinfunction "PB0_54") (pintype "passive"))
    )
    (net (code "56") (name "unconnected-(U5-PB1-Pad55)") (class "Default")
      (node (ref "U5") (pin "55") (pinfunction "PB1_55") (pintype "passive"))
    )
    (net (code "57") (name "unconnected-(U5-PB2-Pad56)") (class "Default")
      (node (ref "U5") (pin "56") (pinfunction "PB2_56") (pintype "passive"))
    )
    (net (code "58") (name "unconnected-(U5-PB3-Pad57)") (class "Default")
      (node (ref "U5") (pin "57") (pinfunction "PB3_57") (pintype "passive"))
    )
    (net (code "59") (name "unconnected-(U5-PB4-Pad58)") (class "Default")
      (node (ref "U5") (pin "58") (pinfunction "PB4_58") (pintype "passive"))
    )
    (net (code "60") (name "unconnected-(U5-PB5-Pad59)") (class "Default")
      (node (ref "U5") (pin "59") (pinfunction "PB5_59") (pintype "passive"))
    )
    (net (code "61") (name "unconnected-(U5-PB6-Pad60)") (class "Default")
      (node (ref "U5") (pin "60") (pinfunction "PB6_60") (pintype "passive"))
    )
    (net (code "62") (name "unconnected-(U5-PC0-Pad46)") (class "Default")
      (node (ref "U5") (pin "46") (pinfunction "PC0_46") (pintype "passive"))
    )
    (net (code "63") (name "unconnected-(U5-PC1-Pad47)") (class "Default")
      (node (ref "U5") (pin "47") (pinfunction "PC1_47") (pintype "passive"))
    )
    (net (code "64") (name "unconnected-(U5-PC2-Pad48)") (class "Default")
      (node (ref "U5") (pin "48") (pinfunction "PC2_48") (pintype "passive"))
    )
    (net (code "65") (name "unconnected-(U5-PC6-Pad52)") (class "Default")
      (node (ref "U5") (pin "52") (pinfunction "PC6_52") (pintype "passive"))
    )
    (net (code "66") (name "unconnected-(U5-PC7-Pad53)") (class "Default")
      (node (ref "U5") (pin "53") (pinfunction "PC7_53") (pintype "passive"))
    )
    (net (code "67") (name "unconnected-(U5-PD0-Pad64)") (class "Default")
      (node (ref "U5") (pin "64") (pinfunction "PD0_64") (pintype "passive"))
    )
    (net (code "68") (name "unconnected-(U5-PD2-Pad66)") (class "Default")
      (node (ref "U5") (pin "66") (pinfunction "PD2_66") (pintype "passive"))
    )
    (net (code "69") (name "unconnected-(U5-PD3-Pad67)") (class "Default")
      (node (ref "U5") (pin "67") (pinfunction "PD3_67") (pintype "passive"))
    )
    (net (code "70") (name "unconnected-(U5-PD4-Pad68)") (class "Default")
      (node (ref "U5") (pin "68") (pinfunction "PD4_68") (pintype "passive"))
    )
    (net (code "71") (name "unconnected-(U5-PD5-Pad69)") (class "Default")
      (node (ref "U5") (pin "69") (pinfunction "PD5_69") (pintype "passive"))
    )
    (net (code "72") (name "unconnected-(U5-PE0-Pad77)") (class "Default")
      (node (ref "U5") (pin "77") (pinfunction "PE0_77") (pintype "passive"))
    )
    (net (code "73") (name "unconnected-(U5-PE1-Pad78)") (class "Default")
      (node (ref "U5") (pin "78") (pinfunction "PE1_78") (pintype "passive"))
    )
    (net (code "74") (name "unconnected-(U5-PE2-Pad79)") (class "Default")
      (node (ref "U5") (pin "79") (pinfunction "PE2_79") (pintype "passive"))
    )
    (net (code "75") (name "unconnected-(U5-PE3-Pad80)") (class "Default")
      (node (ref "U5") (pin "80") (pinfunction "PE3_80") (pintype "passive"))
    )
    (net (code "76") (name "unconnected-(U5-PE4-Pad81)") (class "Default")
      (node (ref "U5") (pin "81") (pinfunction "PE4_81") (pintype "passive"))
    )
    (net (code "77") (name "unconnected-(U5-PE5-Pad82)") (class "Default")
      (node (ref "U5") (pin "82") (pinfunction "PE5_82") (pintype "passive"))
    )
    (net (code "78") (name "unconnected-(U5-PE6-Pad83)") (class "Default")
      (node (ref "U5") (pin "83") (pinfunction "PE6_83") (pintype "passive"))
    )
    (net (code "79") (name "unconnected-(U5-PE7-Pad84)") (class "Default")
      (node (ref "U5") (pin "84") (pinfunction "PE7_84") (pintype "passive"))
    )
    (net (code "80") (name "unconnected-(U5-PF5-Pad95)") (class "Default")
      (node (ref "U5") (pin "95") (pinfunction "PF5_95") (pintype "passive"))
    )
    (net (code "81") (name "unconnected-(U5-PF6-Pad94)") (class "Default")
      (node (ref "U5") (pin "94") (pinfunction "PF6_94") (pintype "passive"))
    )
    (net (code "82") (name "unconnected-(U5-PF7-Pad93)") (class "Default")
      (node (ref "U5") (pin "93") (pinfunction "PF7_93") (pintype "passive"))
    )
    (net (code "83") (name "unconnected-(U5-PG0-Pad70)") (class "Default")
      (node (ref "U5") (pin "70") (pinfunction "PG0_70") (pintype "passive"))
    )
    (net (code "84") (name "unconnected-(U5-PG3-Pad73)") (class "Default")
      (node (ref "U5") (pin "73") (pinfunction "PG3_73") (pintype "passive"))
    )
    (net (code "85") (name "unconnected-(U5-PJ0-Pad45)") (class "Default")
      (node (ref "U5") (pin "45") (pinfunction "PJ0_45") (pintype "passive"))
    )
    (net (code "86") (name "unconnected-(U5-PJ1-Pad44)") (class "Default")
      (node (ref "U5") (pin "44") (pinfunction "PJ1_44") (pintype "passive"))
    )
    (net (code "87") (name "unconnected-(U5-PJ2-Pad43)") (class "Default")
      (node (ref "U5") (pin "43") (pinfunction "PJ2_43") (pintype "passive"))
    )
    (net (code "88") (name "unconnected-(U5-PJ3-Pad42)") (class "Default")
      (node (ref "U5") (pin "42") (pinfunction "PJ3_42") (pintype "passive"))
    )
    (net (code "89") (name "unconnected-(U5-PJ4-Pad41)") (class "Default")
      (node (ref "U5") (pin "41") (pinfunction "PJ4_41") (pintype "passive"))
    )
    (net (code "90") (name "unconnected-(U5-PJ5-Pad40)") (class "Default")
      (node (ref "U5") (pin "40") (pinfunction "PJ5_40") (pintype "passive"))
    )
    (net (code "91") (name "unconnected-(U5-PK0-Pad39)") (class "Default")
      (node (ref "U5") (pin "39") (pinfunction "PK0_39") (pintype "passive"))
    )
    (net (code "92") (name "unconnected-(U5-PK1-Pad38)") (class "Default")
      (node (ref "U5") (pin "38") (pinfunction "PK1_38") (pintype "passive"))
    )
    (net (code "93") (name "unconnected-(U5-PK2-Pad37)") (class "Default")
      (node (ref "U5") (pin "37") (pinfunction "PK2_37") (pintype "passive"))
    )
    (net (code "94") (name "unconnected-(U5-PK3-Pad36)") (class "Default")
      (node (ref "U5") (pin "36") (pinfunction "PK3_36") (pintype "passive"))
    )
    (net (code "95") (name "unconnected-(U5-PK4-Pad35)") (class "Default")
      (node (ref "U5") (pin "35") (pinfunction "PK4_35") (pintype "passive"))
    )
    (net (code "96") (name "unconnected-(U5-PL1-Pad21)") (class "Default")
      (node (ref "U5") (pin "21") (pinfunction "PL1_21") (pintype "passive"))
    )
    (net (code "97") (name "unconnected-(U5-PL2-Pad22)") (class "Default")
      (node (ref "U5") (pin "22") (pinfunction "PL2_22") (pintype "passive"))
    )
    (net (code "98") (name "unconnected-(U5-PL3-Pad23)") (class "Default")
      (node (ref "U5") (pin "23") (pinfunction "PL3_23") (pintype "passive"))
    )
    (net (code "99") (name "unconnected-(U5-PL4-Pad24)") (class "Default")
      (node (ref "U5") (pin "24") (pinfunction "PL4_24") (pintype "passive"))
    )
    (net (code "100") (name "unconnected-(U5-PL5-Pad25)") (class "Default")
      (node (ref "U5") (pin "25") (pinfunction "PL5_25") (pintype "passive"))
    )
    (net (code "101") (name "unconnected-(U5-PL6-Pad26)") (class "Default")
      (node (ref "U5") (pin "26") (pinfunction "PL6_26") (pintype "passive"))
    )
    (net (code "102") (name "unconnected-(U5-PL7-Pad27)") (class "Default")
      (node (ref "U5") (pin "27") (pinfunction "PL7_27") (pintype "passive"))
    )
    (net (code "103") (name "unconnected-(U5-PN2-Pad11)") (class "Default")
      (node (ref "U5") (pin "11") (pinfunction "PN2_11") (pintype "passive"))
    )
    (net (code "104") (name "unconnected-(U5-PN7-Pad61)") (class "Default")
      (node (ref "U5") (pin "61") (pinfunction "PN7_61") (pintype "passive"))
    )
    (net (code "105") (name "unconnected-(U5-PU1-Pad2)") (class "Default")
      (node (ref "U5") (pin "2") (pinfunction "PU1_2") (pintype "passive"))
    )
    (net (code "106") (name "unconnected-(U5-PU2-Pad3)") (class "Default")
      (node (ref "U5") (pin "3") (pinfunction "PU2_3") (pintype "passive"))
    )
    (net (code "107") (name "unconnected-(U5-PU3-Pad4)") (class "Default")
      (node (ref "U5") (pin "4") (pinfunction "PU3_4") (pintype "passive"))
    )
    (net (code "108") (name "unconnected-(U5-PU4-Pad5)") (class "Default")
      (node (ref "U5") (pin "5") (pinfunction "PU4_5") (pintype "passive"))
    )
    (net (code "109") (name "unconnected-(U5-PU5-Pad6)") (class "Default")
      (node (ref "U5") (pin "6") (pinfunction "PU5_6") (pintype "passive"))
    )
    (net (code "110") (name "unconnected-(U5-PU6-Pad7)") (class "Default")
      (node (ref "U5") (pin "7") (pinfunction "PU6_7") (pintype "passive"))
    )
    (net (code "111") (name "unconnected-(U5-PU7-Pad8)") (class "Default")
      (node (ref "U5") (pin "8") (pinfunction "PU7_8") (pintype "passive"))
    )
    (net (code "112") (name "unconnected-(U5-PV0-Pad12)") (class "Default")
      (node (ref "U5") (pin "12") (pinfunction "PV0_12") (pintype "passive"))
    )
    (net (code "113") (name "unconnected-(U5-PV1-Pad13)") (class "Default")
      (node (ref "U5") (pin "13") (pinfunction "PV1_13") (pintype "passive"))
    )
  )
)
